# SensorADC.net
KiCad netlist of a schematic drawn in Altium Designer
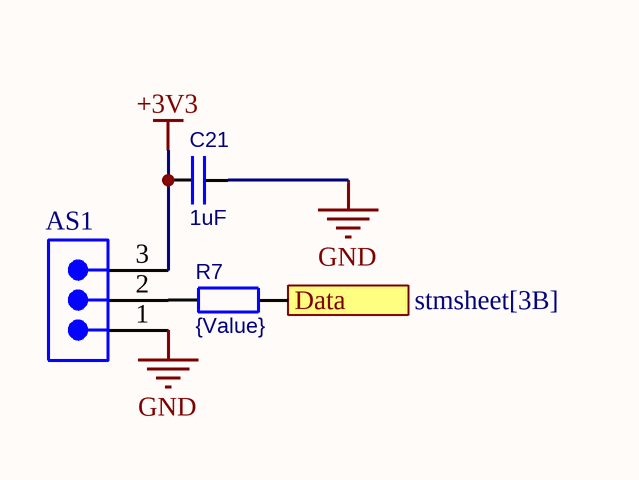
[diagram p0: SensorADC.SchDoc]

(export (version "E")
  (design (tool "Eeschema 10.0.6"))
  (components
    (comp (ref "AS1")
      (value "~")
      (footprint "691321100003")
      (fields (field (name "VOLTAGE") "300V"))
      (libsource (lib "Altium Content Vault") (part "TBL - 1R - 03P - Male"))
    )
    (comp (ref "C21")
      (value "1uF")
      (footprint "C0603")
      (description "Capacitor")
      (libsource (lib "General") (part "C"))
    )
    (comp (ref "R7")
      (value "{Value}")
      (footprint "R0603")
      (description "R")
      (libsource (lib "General") (part "R"))
    )
  )
  (nets
    (net (code "1") (name "+3V3") (class "Default")
      (node (ref "AS1") (pin "3") (pinfunction "3_3") (pintype "passive"))
      (node (ref "C21") (pin "1") (pinfunction "1_1") (pintype "passive"))
    )
    (net (code "2") (name "/Data") (class "Default") (node (ref "R7") (pin "2") (pintype "passive")))
    (net (code "3") (name "GND") (class "Default")
      (node (ref "AS1") (pin "1") (pinfunction "1_1") (pintype "passive"))
      (node (ref "C21") (pin "2") (pinfunction "2_2") (pintype "passive"))
    )
    (net (code "4") (name "Net-(AS1-Pad2)") (class "Default")
      (node (ref "AS1") (pin "2") (pinfunction "2_2") (pintype "passive"))
      (node (ref "R7") (pin "1") (pintype "passive"))
    )
  )
)
